# digit.net
KiCad netlist of a schematic drawn in EAGLE
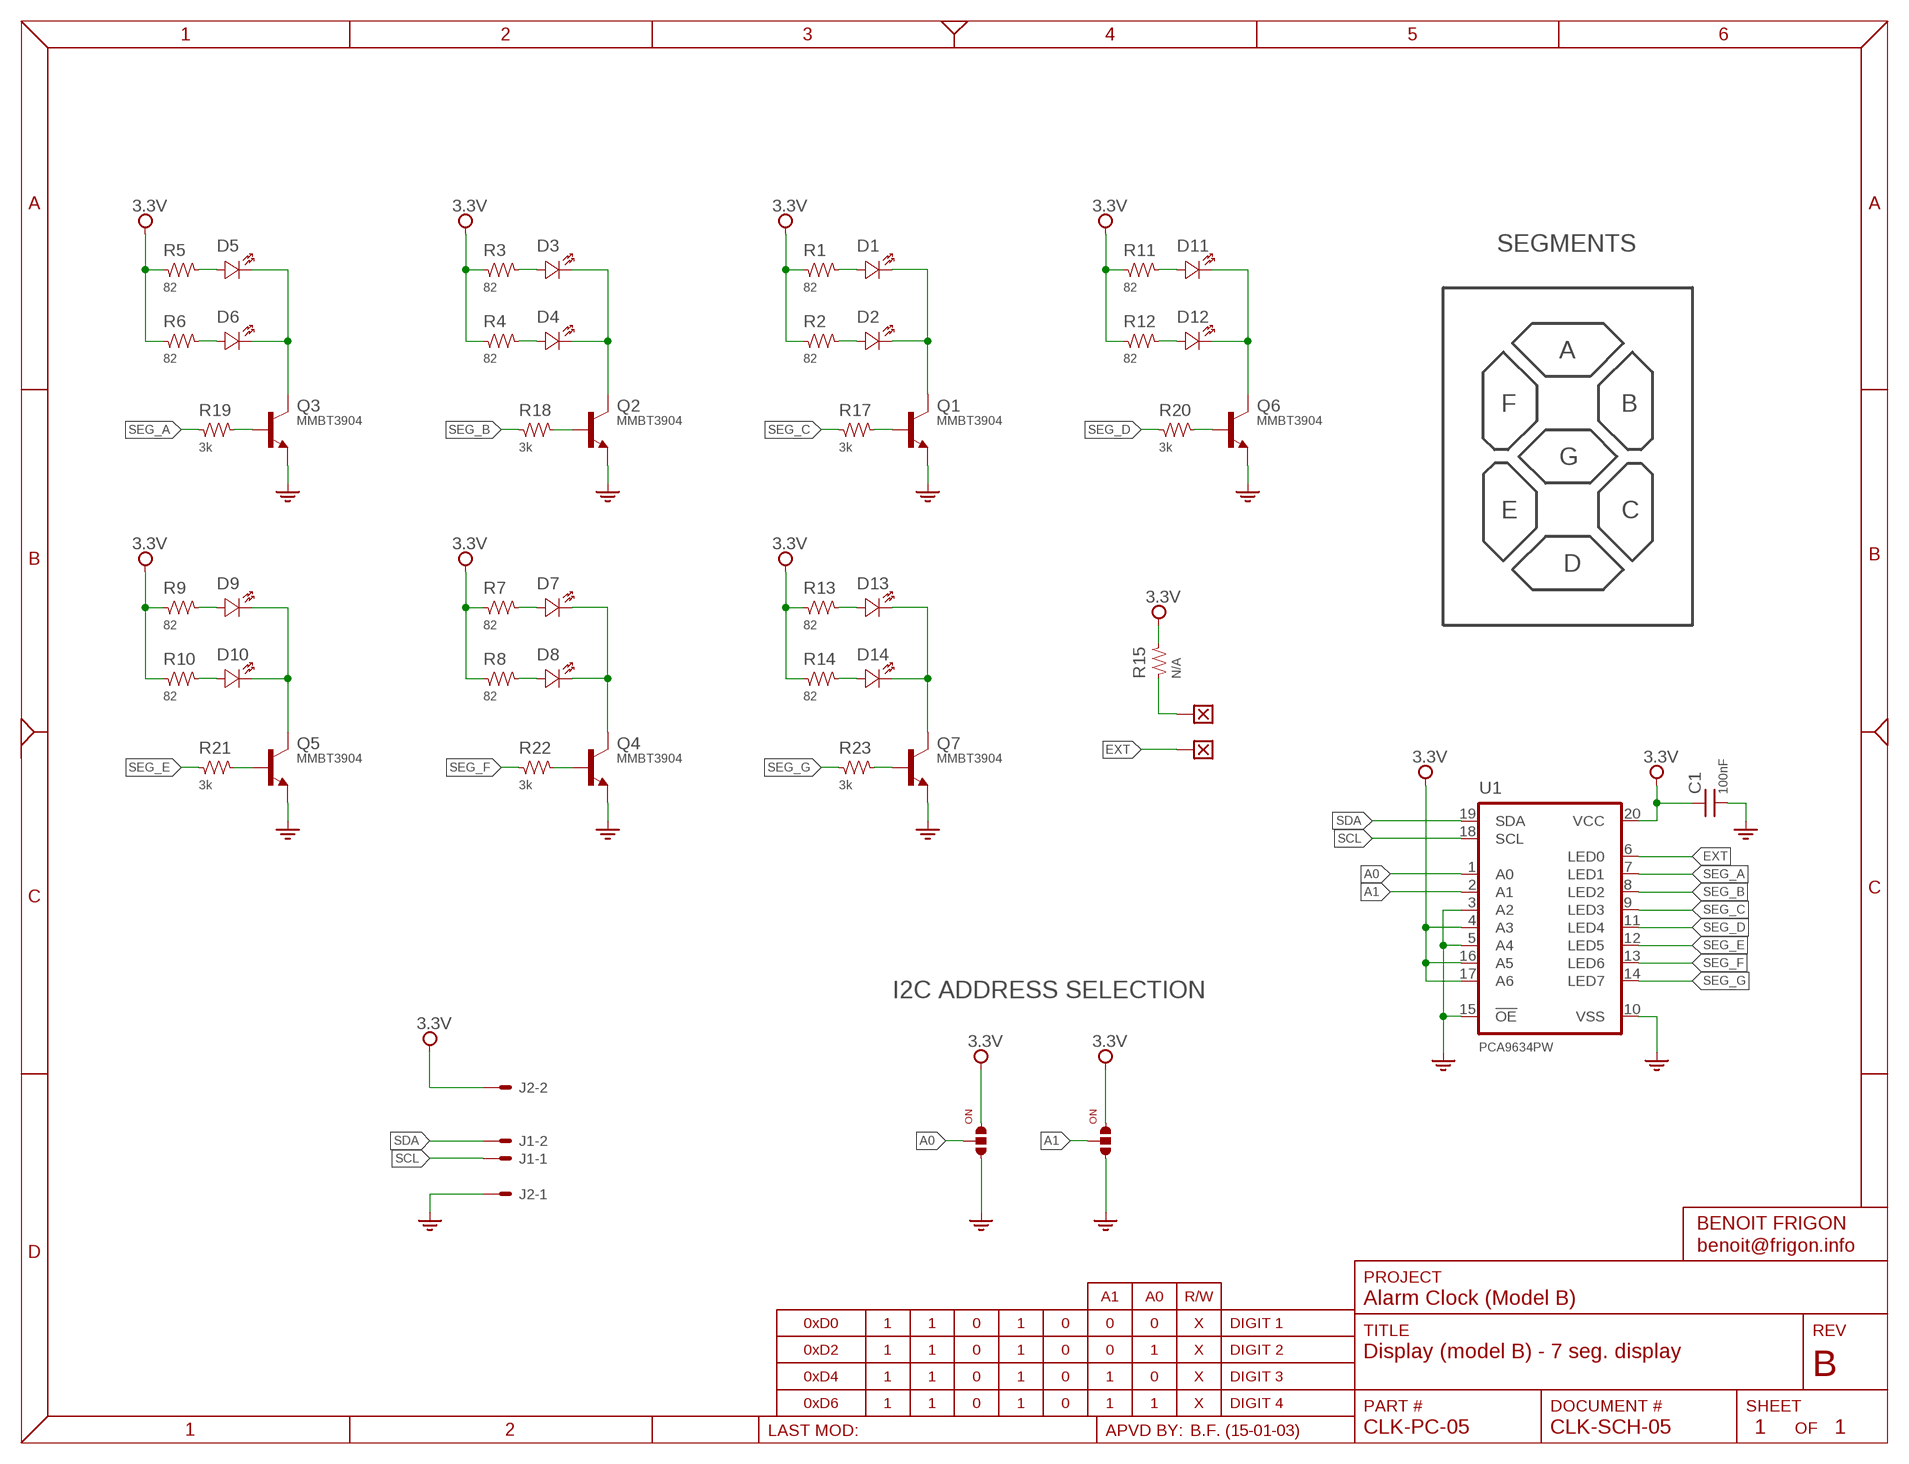
[diagram p0: schematic, sheet 1]

(export (version "E")
  (design (tool "Eeschema 10.0.6"))
  (components
    (comp (ref "C1")
      (value "100nF")
      (footprint "eagle-import:SMD_0603")
      (libsource (lib "eagle-import") (part "CAP-0603"))
    )
    (comp (ref "D1")
      (value "Orange")
      (footprint "eagle-import:CHIPLED_0805")
      (fields
        (field (name "COLOR") "Orange")
        (field (name "MFG") "Kingbright")
        (field (name "PART_NO") "APT2012SECK/J4-PRV")
      )
      (libsource (lib "eagle-import") (part "LED-0805"))
    )
    (comp (ref "D2")
      (value "Orange")
      (footprint "eagle-import:CHIPLED_0805")
      (fields
        (field (name "COLOR") "Orange")
        (field (name "MFG") "Kingbright")
        (field (name "PART_NO") "APT2012SECK/J4-PRV")
      )
      (libsource (lib "eagle-import") (part "LED-0805"))
    )
    (comp (ref "D3")
      (value "Orange")
      (footprint "eagle-import:CHIPLED_0805")
      (fields
        (field (name "COLOR") "Orange")
        (field (name "MFG") "Kingbright")
        (field (name "PART_NO") "APT2012SECK/J4-PRV")
      )
      (libsource (lib "eagle-import") (part "LED-0805"))
    )
    (comp (ref "D4")
      (value "Orange")
      (footprint "eagle-import:CHIPLED_0805")
      (description "{DESCRIPTION} Chip 0805 - {ATTR:COLOR}")
      (fields
        (field (name "COLOR") "Orange")
        (field (name "MFG") "Kingbright")
        (field (name "PACKAGE") "SMT 0805")
        (field (name "PART_NO") "APT2012SECK/J4-PRV")
      )
      (libsource (lib "eagle-import") (part "LED-0805"))
    )
    (comp (ref "D5")
      (value "Red")
      (footprint "eagle-import:CHIPLED_0805")
      (description "{DESCRIPTION} Chip 0805 - {ATTR:COLOR}")
      (fields
        (field (name "COLOR") "Orange")
        (field (name "MFG") "Kingbright")
        (field (name "PACKAGE") "SMT 0805")
        (field (name "PART_NO") "APT2012SECK/J4-PRV")
      )
      (libsource (lib "eagle-import") (part "LED-0805"))
    )
    (comp (ref "D6")
      (value "orange")
      (footprint "eagle-import:CHIPLED_0805")
      (description "{DESCRIPTION} Chip 0805 - {ATTR:COLOR}")
      (fields
        (field (name "COLOR") "Orange")
        (field (name "MFG") "Kingbright")
        (field (name "PACKAGE") "SMT 0805")
        (field (name "PART_NO") "APT2012SECK/J4-PRV")
      )
      (libsource (lib "eagle-import") (part "LED-0805"))
    )
    (comp (ref "D7")
      (value "Orange")
      (footprint "eagle-import:CHIPLED_0805")
      (fields
        (field (name "COLOR") "Orange")
        (field (name "MFG") "Kingbright")
        (field (name "PART_NO") "APT2012SECK/J4-PRV")
      )
      (libsource (lib "eagle-import") (part "LED-0805"))
    )
    (comp (ref "D8")
      (value "Orange")
      (footprint "eagle-import:CHIPLED_0805")
      (fields
        (field (name "COLOR") "Orange")
        (field (name "MFG") "Kingbright")
        (field (name "PART_NO") "APT2012SECK/J4-PRV")
      )
      (libsource (lib "eagle-import") (part "LED-0805"))
    )
    (comp (ref "D9")
      (value "Orange")
      (footprint "eagle-import:CHIPLED_0805")
      (fields
        (field (name "COLOR") "Orange")
        (field (name "MFG") "Kingbright")
        (field (name "PART_NO") "APT2012SECK/J4-PRV")
      )
      (libsource (lib "eagle-import") (part "LED-0805"))
    )
    (comp (ref "D10")
      (value "Orange")
      (footprint "eagle-import:CHIPLED_0805")
      (fields
        (field (name "COLOR") "Orange")
        (field (name "MFG") "Kingbright")
        (field (name "PART_NO") "APT2012SECK/J4-PRV")
      )
      (libsource (lib "eagle-import") (part "LED-0805"))
    )
    (comp (ref "D11")
      (value "Orange")
      (footprint "eagle-import:CHIPLED_0805")
      (description "{DESCRIPTION} Chip 0805 - {ATTR:COLOR}")
      (fields
        (field (name "COLOR") "Orange")
        (field (name "MFG") "Kingbright")
        (field (name "PACKAGE") "SMT 0805")
        (field (name "PART_NO") "APT2012SECK/J4-PRV")
      )
      (libsource (lib "eagle-import") (part "LED-0805"))
    )
    (comp (ref "D12")
      (value "Orange")
      (footprint "eagle-import:CHIPLED_0805")
      (description "{DESCRIPTION} Chip 0805 - {ATTR:COLOR}")
      (fields
        (field (name "COLOR") "Orange")
        (field (name "MFG") "Kingbright")
        (field (name "PACKAGE") "SMT 0805")
        (field (name "PART_NO") "APT2012SECK/J4-PRV")
      )
      (libsource (lib "eagle-import") (part "LED-0805"))
    )
    (comp (ref "D13")
      (value "Orange")
      (footprint "eagle-import:CHIPLED_0805")
      (description "{DESCRIPTION} Chip 0805 - {ATTR:COLOR}")
      (fields
        (field (name "COLOR") "Orange")
        (field (name "MFG") "Kingbright")
        (field (name "PACKAGE") "SMT 0805")
        (field (name "PART_NO") "APT2012SECK/J4-PRV")
      )
      (libsource (lib "eagle-import") (part "LED-0805"))
    )
    (comp (ref "D14")
      (value "Orange")
      (footprint "eagle-import:CHIPLED_0805")
      (description "{DESCRIPTION} Chip 0805 - {ATTR:COLOR}")
      (fields
        (field (name "COLOR") "Orange")
        (field (name "MFG") "Kingbright")
        (field (name "PACKAGE") "SMT 0805")
        (field (name "PART_NO") "APT2012SECK/J4-PRV")
      )
      (libsource (lib "eagle-import") (part "LED-0805"))
    )
    (comp (ref "J1")
      (value "DL-100-HEADER-02-EDGE")
      (footprint "eagle-import:HDR100-EDGE-2")
      (fields (field (name "MFG") "Molex") (field (name "PART_NO") "3-644456-2"))
      (libsource (lib "eagle-import") (part "DL-100-HEADER-02-EDGE"))
    )
    (comp (ref "J2")
      (value "DL-100-HEADER-02-EDGE")
      (footprint "eagle-import:HDR100-EDGE-2")
      (fields (field (name "MFG") "Molex") (field (name "PART_NO") "3-644456-2"))
      (libsource (lib "eagle-import") (part "DL-100-HEADER-02-EDGE"))
    )
    (comp (ref "J10")
      (value "SOLDER_JUMPER_3")
      (footprint "eagle-import:SOLDER_JUMPER_3")
      (libsource (lib "eagle-import") (part "SOLDER_JUMPER_3"))
    )
    (comp (ref "J11")
      (value "SOLDER_JUMPER_3")
      (footprint "eagle-import:SOLDER_JUMPER_3")
      (libsource (lib "eagle-import") (part "SOLDER_JUMPER_3"))
    )
    (comp (ref "Q1")
      (value "MMBT3904")
      (footprint "eagle-import:SOT23")
      (libsource (lib "eagle-import") (part "MMBT3904"))
    )
    (comp (ref "Q2")
      (value "MMBT3904")
      (footprint "eagle-import:SOT23")
      (libsource (lib "eagle-import") (part "MMBT3904"))
    )
    (comp (ref "Q3")
      (value "MMBT3904")
      (footprint "eagle-import:SOT23")
      (libsource (lib "eagle-import") (part "MMBT3904"))
    )
    (comp (ref "Q4")
      (value "MMBT3904")
      (footprint "eagle-import:SOT23")
      (libsource (lib "eagle-import") (part "MMBT3904"))
    )
    (comp (ref "Q5")
      (value "MMBT3904")
      (footprint "eagle-import:SOT23")
      (libsource (lib "eagle-import") (part "MMBT3904"))
    )
    (comp (ref "Q6")
      (value "MMBT3904")
      (footprint "eagle-import:SOT23")
      (libsource (lib "eagle-import") (part "MMBT3904"))
    )
    (comp (ref "Q7")
      (value "MMBT3904")
      (footprint "eagle-import:SOT23")
      (libsource (lib "eagle-import") (part "MMBT3904"))
    )
    (comp (ref "R1")
      (value "82")
      (footprint "eagle-import:SMD_0603")
      (libsource (lib "eagle-import") (part "RES-0603"))
    )
    (comp (ref "R2")
      (value "82")
      (footprint "eagle-import:SMD_0603")
      (description "{DESCRIPTION} - SMT 0603 - {VALUE}")
      (fields (field (name "PACKAGE") "SMT 0603"))
      (libsource (lib "eagle-import") (part "RES-0603"))
    )
    (comp (ref "R3")
      (value "82")
      (footprint "eagle-import:SMD_0603")
      (description "{DESCRIPTION} - SMT 0603 - {VALUE}")
      (fields (field (name "PACKAGE") "SMT 0603"))
      (libsource (lib "eagle-import") (part "RES-0603"))
    )
    (comp (ref "R4")
      (value "82")
      (footprint "eagle-import:SMD_0603")
      (description "{DESCRIPTION} - SMT 0603 - {VALUE}")
      (fields (field (name "PACKAGE") "SMT 0603"))
      (libsource (lib "eagle-import") (part "RES-0603"))
    )
    (comp (ref "R5")
      (value "82")
      (footprint "eagle-import:SMD_0603")
      (description "{DESCRIPTION} - SMT 0603 - {VALUE}")
      (fields (field (name "PACKAGE") "SMT 0603"))
      (libsource (lib "eagle-import") (part "RES-0603"))
    )
    (comp (ref "R6")
      (value "82")
      (footprint "eagle-import:SMD_0603")
      (description "{DESCRIPTION} - SMT 0603 - {VALUE}")
      (fields (field (name "PACKAGE") "SMT 0603"))
      (libsource (lib "eagle-import") (part "RES-0603"))
    )
    (comp (ref "R7")
      (value "82")
      (footprint "eagle-import:SMD_0603")
      (description "{DESCRIPTION} - SMT 0603 - {VALUE}")
      (fields (field (name "PACKAGE") "SMT 0603"))
      (libsource (lib "eagle-import") (part "RES-0603"))
    )
    (comp (ref "R8")
      (value "82")
      (footprint "eagle-import:SMD_0603")
      (description "{DESCRIPTION} - SMT 0603 - {VALUE}")
      (fields (field (name "PACKAGE") "SMT 0603"))
      (libsource (lib "eagle-import") (part "RES-0603"))
    )
    (comp (ref "R9")
      (value "82")
      (footprint "eagle-import:SMD_0603")
      (description "{DESCRIPTION} - SMT 0603 - {VALUE}")
      (fields (field (name "PACKAGE") "SMT 0603"))
      (libsource (lib "eagle-import") (part "RES-0603"))
    )
    (comp (ref "R10")
      (value "82")
      (footprint "eagle-import:SMD_0603")
      (description "{DESCRIPTION} - SMT 0603 - {VALUE}")
      (fields (field (name "PACKAGE") "SMT 0603"))
      (libsource (lib "eagle-import") (part "RES-0603"))
    )
    (comp (ref "R11")
      (value "82")
      (footprint "eagle-import:SMD_0603")
      (description "{DESCRIPTION} - SMT 0603 - {VALUE}")
      (fields (field (name "PACKAGE") "SMT 0603"))
      (libsource (lib "eagle-import") (part "RES-0603"))
    )
    (comp (ref "R12")
      (value "82")
      (footprint "eagle-import:SMD_0603")
      (description "{DESCRIPTION} - SMT 0603 - {VALUE}")
      (fields (field (name "PACKAGE") "SMT 0603"))
      (libsource (lib "eagle-import") (part "RES-0603"))
    )
    (comp (ref "R13")
      (value "82")
      (footprint "eagle-import:SMD_0603")
      (description "{DESCRIPTION} - SMT 0603 - {VALUE}")
      (fields (field (name "PACKAGE") "SMT 0603"))
      (libsource (lib "eagle-import") (part "RES-0603"))
    )
    (comp (ref "R14")
      (value "82")
      (footprint "eagle-import:SMD_0603")
      (description "{DESCRIPTION} - SMT 0603 - {VALUE}")
      (fields (field (name "PACKAGE") "SMT 0603"))
      (libsource (lib "eagle-import") (part "RES-0603"))
    )
    (comp (ref "R15")
      (value "N/A")
      (footprint "eagle-import:SMD_0603")
      (libsource (lib "eagle-import") (part "RES-0603"))
    )
    (comp (ref "R17")
      (value "3k")
      (footprint "eagle-import:SMD_0603")
      (libsource (lib "eagle-import") (part "RES-0603"))
    )
    (comp (ref "R18")
      (value "3k")
      (footprint "eagle-import:SMD_0603")
      (description "{DESCRIPTION} - SMT 0603 - {VALUE}")
      (fields (field (name "PACKAGE") "SMT 0603"))
      (libsource (lib "eagle-import") (part "RES-0603"))
    )
    (comp (ref "R19")
      (value "3k")
      (footprint "eagle-import:SMD_0603")
      (description "{DESCRIPTION} - SMT 0603 - {VALUE}")
      (fields (field (name "PACKAGE") "SMT 0603"))
      (libsource (lib "eagle-import") (part "RES-0603"))
    )
    (comp (ref "R20")
      (value "3k")
      (footprint "eagle-import:SMD_0603")
      (description "{DESCRIPTION} - SMT 0603 - {VALUE}")
      (fields (field (name "PACKAGE") "SMT 0603"))
      (libsource (lib "eagle-import") (part "RES-0603"))
    )
    (comp (ref "R21")
      (value "3k")
      (footprint "eagle-import:SMD_0603")
      (description "{DESCRIPTION} - SMT 0603 - {VALUE}")
      (fields (field (name "PACKAGE") "SMT 0603"))
      (libsource (lib "eagle-import") (part "RES-0603"))
    )
    (comp (ref "R22")
      (value "3k")
      (footprint "eagle-import:SMD_0603")
      (description "{DESCRIPTION} - SMT 0603 - {VALUE}")
      (fields (field (name "PACKAGE") "SMT 0603"))
      (libsource (lib "eagle-import") (part "RES-0603"))
    )
    (comp (ref "R23")
      (value "3k")
      (footprint "eagle-import:SMD_0603")
      (description "{DESCRIPTION} - SMT 0603 - {VALUE}")
      (fields (field (name "PACKAGE") "SMT 0603"))
      (libsource (lib "eagle-import") (part "RES-0603"))
    )
    (comp (ref "U1")
      (value "PCA9634PW")
      (footprint "eagle-import:TSSOP20")
      (fields (field (name "MFG") "NXP Semiconductors"))
      (libsource (lib "eagle-import") (part "PCA9634PW"))
    )
    (comp (ref "W5")
      (value "WIRE")
      (footprint "eagle-import:WIRE_SMT")
      (fields (field (name "BOM") "False"))
      (libsource (lib "eagle-import") (part "WIRE"))
    )
    (comp (ref "W6")
      (value "WIRE")
      (footprint "eagle-import:WIRE_SMT")
      (fields (field (name "BOM") "False"))
      (libsource (lib "eagle-import") (part "WIRE"))
    )
  )
  (nets
    (net (code "1") (name "3.3V") (class "Default")
      (node (ref "C1") (pin "1") (pinfunction "1_1") (pintype "passive"))
      (node (ref "J10") (pin "1") (pinfunction "1_1") (pintype "bidirectional"))
      (node (ref "J11") (pin "1") (pinfunction "1_1") (pintype "bidirectional"))
      (node (ref "J2") (pin "2") (pinfunction "S_2") (pintype "bidirectional"))
      (node (ref "R1") (pin "1") (pinfunction "1_1") (pintype "passive"))
      (node (ref "R10") (pin "1") (pinfunction "1_1") (pintype "passive"))
      (node (ref "R11") (pin "1") (pinfunction "1_1") (pintype "passive"))
      (node (ref "R12") (pin "1") (pinfunction "1_1") (pintype "passive"))
      (node (ref "R13") (pin "1") (pinfunction "1_1") (pintype "passive"))
      (node (ref "R14") (pin "1") (pinfunction "1_1") (pintype "passive"))
      (node (ref "R15") (pin "2") (pinfunction "2_2") (pintype "passive"))
      (node (ref "R2") (pin "1") (pinfunction "1_1") (pintype "passive"))
      (node (ref "R3") (pin "1") (pinfunction "1_1") (pintype "passive"))
      (node (ref "R4") (pin "1") (pinfunction "1_1") (pintype "passive"))
      (node (ref "R5") (pin "1") (pinfunction "1_1") (pintype "passive"))
      (node (ref "R6") (pin "1") (pinfunction "1_1") (pintype "passive"))
      (node (ref "R7") (pin "1") (pinfunction "1_1") (pintype "passive"))
      (node (ref "R8") (pin "1") (pinfunction "1_1") (pintype "passive"))
      (node (ref "R9") (pin "1") (pinfunction "1_1") (pintype "passive"))
      (node (ref "U1") (pin "16") (pinfunction "A5_16") (pintype "bidirectional"))
      (node (ref "U1") (pin "17") (pinfunction "A6_17") (pintype "bidirectional"))
      (node (ref "U1") (pin "20") (pinfunction "VCC_20") (pintype "bidirectional"))
      (node (ref "U1") (pin "4") (pinfunction "A3_4") (pintype "bidirectional"))
    )
    (net (code "2") (name "A0") (class "Default")
      (node (ref "J10") (pin "2") (pinfunction "2_2") (pintype "bidirectional"))
      (node (ref "U1") (pin "1") (pinfunction "A0_1") (pintype "bidirectional"))
    )
    (net (code "3") (name "A1") (class "Default")
      (node (ref "J11") (pin "2") (pinfunction "2_2") (pintype "bidirectional"))
      (node (ref "U1") (pin "2") (pinfunction "A1_2") (pintype "bidirectional"))
    )
    (net (code "4") (name "EXT") (class "Default")
      (node (ref "U1") (pin "6") (pinfunction "LED0_6") (pintype "bidirectional"))
      (node (ref "W5") (pin "1") (pinfunction "P$1_1") (pintype "bidirectional"))
    )
    (net (code "5") (name "GND") (class "Default")
      (node (ref "C1") (pin "2") (pinfunction "2_2") (pintype "passive"))
      (node (ref "J10") (pin "3") (pinfunction "3_3") (pintype "bidirectional"))
      (node (ref "J11") (pin "3") (pinfunction "3_3") (pintype "bidirectional"))
      (node (ref "J2") (pin "1") (pinfunction "S_1") (pintype "bidirectional"))
      (node (ref "Q1") (pin "2") (pinfunction "E_2") (pintype "passive"))
      (node (ref "Q2") (pin "2") (pinfunction "E_2") (pintype "passive"))
      (node (ref "Q3") (pin "2") (pinfunction "E_2") (pintype "passive"))
      (node (ref "Q4") (pin "2") (pinfunction "E_2") (pintype "passive"))
      (node (ref "Q5") (pin "2") (pinfunction "E_2") (pintype "passive"))
      (node (ref "Q6") (pin "2") (pinfunction "E_2") (pintype "passive"))
      (node (ref "Q7") (pin "2") (pinfunction "E_2") (pintype "passive"))
      (node (ref "U1") (pin "10") (pinfunction "VSS_10") (pintype "bidirectional"))
      (node (ref "U1") (pin "15") (pinfunction "~{OE}_15") (pintype "bidirectional"))
      (node (ref "U1") (pin "3") (pinfunction "A2_3") (pintype "bidirectional"))
      (node (ref "U1") (pin "5") (pinfunction "A4_5") (pintype "bidirectional"))
    )
    (net (code "6") (name "Net-(D1-PadA)") (class "Default")
      (node (ref "D1") (pin "A") (pinfunction "A_A") (pintype "passive"))
      (node (ref "R1") (pin "2") (pinfunction "2_2") (pintype "passive"))
    )
    (net (code "7") (name "Net-(D2-PadA)") (class "Default")
      (node (ref "D2") (pin "A") (pinfunction "A_A") (pintype "passive"))
      (node (ref "R2") (pin "2") (pinfunction "2_2") (pintype "passive"))
    )
    (net (code "8") (name "Net-(D3-PadA)") (class "Default")
      (node (ref "D3") (pin "A") (pinfunction "A_A") (pintype "passive"))
      (node (ref "R3") (pin "2") (pinfunction "2_2") (pintype "passive"))
    )
    (net (code "9") (name "Net-(D4-PadA)") (class "Default")
      (node (ref "D4") (pin "A") (pinfunction "A_A") (pintype "passive"))
      (node (ref "R4") (pin "2") (pinfunction "2_2") (pintype "passive"))
    )
    (net (code "10") (name "Net-(D5-PadA)") (class "Default")
      (node (ref "D5") (pin "A") (pinfunction "A_A") (pintype "passive"))
      (node (ref "R5") (pin "2") (pinfunction "2_2") (pintype "passive"))
    )
    (net (code "11") (name "Net-(D6-PadA)") (class "Default")
      (node (ref "D6") (pin "A") (pinfunction "A_A") (pintype "passive"))
      (node (ref "R6") (pin "2") (pinfunction "2_2") (pintype "passive"))
    )
    (net (code "12") (name "Net-(D7-PadA)") (class "Default")
      (node (ref "D7") (pin "A") (pinfunction "A_A") (pintype "passive"))
      (node (ref "R7") (pin "2") (pinfunction "2_2") (pintype "passive"))
    )
    (net (code "13") (name "Net-(D8-PadA)") (class "Default")
      (node (ref "D8") (pin "A") (pinfunction "A_A") (pintype "passive"))
      (node (ref "R8") (pin "2") (pinfunction "2_2") (pintype "passive"))
    )
    (net (code "14") (name "Net-(D9-PadA)") (class "Default")
      (node (ref "D9") (pin "A") (pinfunction "A_A") (pintype "passive"))
      (node (ref "R9") (pin "2") (pinfunction "2_2") (pintype "passive"))
    )
    (net (code "15") (name "Net-(D10-PadA)") (class "Default")
      (node (ref "D10") (pin "A") (pinfunction "A_A") (pintype "passive"))
      (node (ref "R10") (pin "2") (pinfunction "2_2") (pintype "passive"))
    )
    (net (code "16") (name "Net-(D11-PadA)") (class "Default")
      (node (ref "D11") (pin "A") (pinfunction "A_A") (pintype "passive"))
      (node (ref "R11") (pin "2") (pinfunction "2_2") (pintype "passive"))
    )
    (net (code "17") (name "Net-(D12-PadA)") (class "Default")
      (node (ref "D12") (pin "A") (pinfunction "A_A") (pintype "passive"))
      (node (ref "R12") (pin "2") (pinfunction "2_2") (pintype "passive"))
    )
    (net (code "18") (name "Net-(D13-PadA)") (class "Default")
      (node (ref "D13") (pin "A") (pinfunction "A_A") (pintype "passive"))
      (node (ref "R13") (pin "2") (pinfunction "2_2") (pintype "passive"))
    )
    (net (code "19") (name "Net-(D14-PadA)") (class "Default")
      (node (ref "D14") (pin "A") (pinfunction "A_A") (pintype "passive"))
      (node (ref "R14") (pin "2") (pinfunction "2_2") (pintype "passive"))
    )
    (net (code "20") (name "Net-(Q1-B)") (class "Default")
      (node (ref "Q1") (pin "1") (pinfunction "B_1") (pintype "passive"))
      (node (ref "R17") (pin "2") (pinfunction "2_2") (pintype "passive"))
    )
    (net (code "21") (name "Net-(Q1-C)") (class "Default")
      (node (ref "D1") (pin "K") (pinfunction "K_K") (pintype "passive"))
      (node (ref "D2") (pin "K") (pinfunction "K_K") (pintype "passive"))
      (node (ref "Q1") (pin "3") (pinfunction "C_3") (pintype "passive"))
    )
    (net (code "22") (name "Net-(Q2-B)") (class "Default")
      (node (ref "Q2") (pin "1") (pinfunction "B_1") (pintype "passive"))
      (node (ref "R18") (pin "2") (pinfunction "2_2") (pintype "passive"))
    )
    (net (code "23") (name "Net-(Q2-C)") (class "Default")
      (node (ref "D3") (pin "K") (pinfunction "K_K") (pintype "passive"))
      (node (ref "D4") (pin "K") (pinfunction "K_K") (pintype "passive"))
      (node (ref "Q2") (pin "3") (pinfunction "C_3") (pintype "passive"))
    )
    (net (code "24") (name "Net-(Q3-B)") (class "Default")
      (node (ref "Q3") (pin "1") (pinfunction "B_1") (pintype "passive"))
      (node (ref "R19") (pin "2") (pinfunction "2_2") (pintype "passive"))
    )
    (net (code "25") (name "Net-(Q3-C)") (class "Default")
      (node (ref "D5") (pin "K") (pinfunction "K_K") (pintype "passive"))
      (node (ref "D6") (pin "K") (pinfunction "K_K") (pintype "passive"))
      (node (ref "Q3") (pin "3") (pinfunction "C_3") (pintype "passive"))
    )
    (net (code "26") (name "Net-(Q4-B)") (class "Default")
      (node (ref "Q4") (pin "1") (pinfunction "B_1") (pintype "passive"))
      (node (ref "R22") (pin "2") (pinfunction "2_2") (pintype "passive"))
    )
    (net (code "27") (name "Net-(Q4-C)") (class "Default")
      (node (ref "D7") (pin "K") (pinfunction "K_K") (pintype "passive"))
      (node (ref "D8") (pin "K") (pinfunction "K_K") (pintype "passive"))
      (node (ref "Q4") (pin "3") (pinfunction "C_3") (pintype "passive"))
    )
    (net (code "28") (name "Net-(Q5-B)") (class "Default")
      (node (ref "Q5") (pin "1") (pinfunction "B_1") (pintype "passive"))
      (node (ref "R21") (pin "2") (pinfunction "2_2") (pintype "passive"))
    )
    (net (code "29") (name "Net-(Q5-C)") (class "Default")
      (node (ref "D10") (pin "K") (pinfunction "K_K") (pintype "passive"))
      (node (ref "D9") (pin "K") (pinfunction "K_K") (pintype "passive"))
      (node (ref "Q5") (pin "3") (pinfunction "C_3") (pintype "passive"))
    )
    (net (code "30") (name "Net-(Q6-B)") (class "Default")
      (node (ref "Q6") (pin "1") (pinfunction "B_1") (pintype "passive"))
      (node (ref "R20") (pin "2") (pinfunction "2_2") (pintype "passive"))
    )
    (net (code "31") (name "Net-(Q6-C)") (class "Default")
      (node (ref "D11") (pin "K") (pinfunction "K_K") (pintype "passive"))
      (node (ref "D12") (pin "K") (pinfunction "K_K") (pintype "passive"))
      (node (ref "Q6") (pin "3") (pinfunction "C_3") (pintype "passive"))
    )
    (net (code "32") (name "Net-(Q7-B)") (class "Default")
      (node (ref "Q7") (pin "1") (pinfunction "B_1") (pintype "passive"))
      (node (ref "R23") (pin "2") (pinfunction "2_2") (pintype "passive"))
    )
    (net (code "33") (name "Net-(Q7-C)") (class "Default")
      (node (ref "D13") (pin "K") (pinfunction "K_K") (pintype "passive"))
      (node (ref "D14") (pin "K") (pinfunction "K_K") (pintype "passive"))
      (node (ref "Q7") (pin "3") (pinfunction "C_3") (pintype "passive"))
    )
    (net (code "34") (name "Net-(W6-P$1)") (class "Default")
      (node (ref "R15") (pin "1") (pinfunction "1_1") (pintype "passive"))
      (node (ref "W6") (pin "1") (pinfunction "P$1_1") (pintype "bidirectional"))
    )
    (net (code "35") (name "SCL") (class "Default")
      (node (ref "J1") (pin "1") (pinfunction "S_1") (pintype "bidirectional"))
      (node (ref "U1") (pin "18") (pinfunction "SCL_18") (pintype "bidirectional"))
    )
    (net (code "36") (name "SDA") (class "Default")
      (node (ref "J1") (pin "2") (pinfunction "S_2") (pintype "bidirectional"))
      (node (ref "U1") (pin "19") (pinfunction "SDA_19") (pintype "bidirectional"))
    )
    (net (code "37") (name "SEG_A") (class "Default")
      (node (ref "R19") (pin "1") (pinfunction "1_1") (pintype "passive"))
      (node (ref "U1") (pin "7") (pinfunction "LED1_7") (pintype "bidirectional"))
    )
    (net (code "38") (name "SEG_B") (class "Default")
      (node (ref "R18") (pin "1") (pinfunction "1_1") (pintype "passive"))
      (node (ref "U1") (pin "8") (pinfunction "LED2_8") (pintype "bidirectional"))
    )
    (net (code "39") (name "SEG_C") (class "Default")
      (node (ref "R17") (pin "1") (pinfunction "1_1") (pintype "passive"))
      (node (ref "U1") (pin "9") (pinfunction "LED3_9") (pintype "bidirectional"))
    )
    (net (code "40") (name "SEG_D") (class "Default")
      (node (ref "R20") (pin "1") (pinfunction "1_1") (pintype "passive"))
      (node (ref "U1") (pin "11") (pinfunction "LED4_11") (pintype "bidirectional"))
    )
    (net (code "41") (name "SEG_E") (class "Default")
      (node (ref "R21") (pin "1") (pinfunction "1_1") (pintype "passive"))
      (node (ref "U1") (pin "12") (pinfunction "LED5_12") (pintype "bidirectional"))
    )
    (net (code "42") (name "SEG_F") (class "Default")
      (node (ref "R22") (pin "1") (pinfunction "1_1") (pintype "passive"))
      (node (ref "U1") (pin "13") (pinfunction "LED6_13") (pintype "bidirectional"))
    )
    (net (code "43") (name "SEG_G") (class "Default")
      (node (ref "R23") (pin "1") (pinfunction "1_1") (pintype "passive"))
      (node (ref "U1") (pin "14") (pinfunction "LED7_14") (pintype "bidirectional"))
    )
  )
)
